# Port_Power.net
KiCad netlist of a schematic drawn in Altium Designer
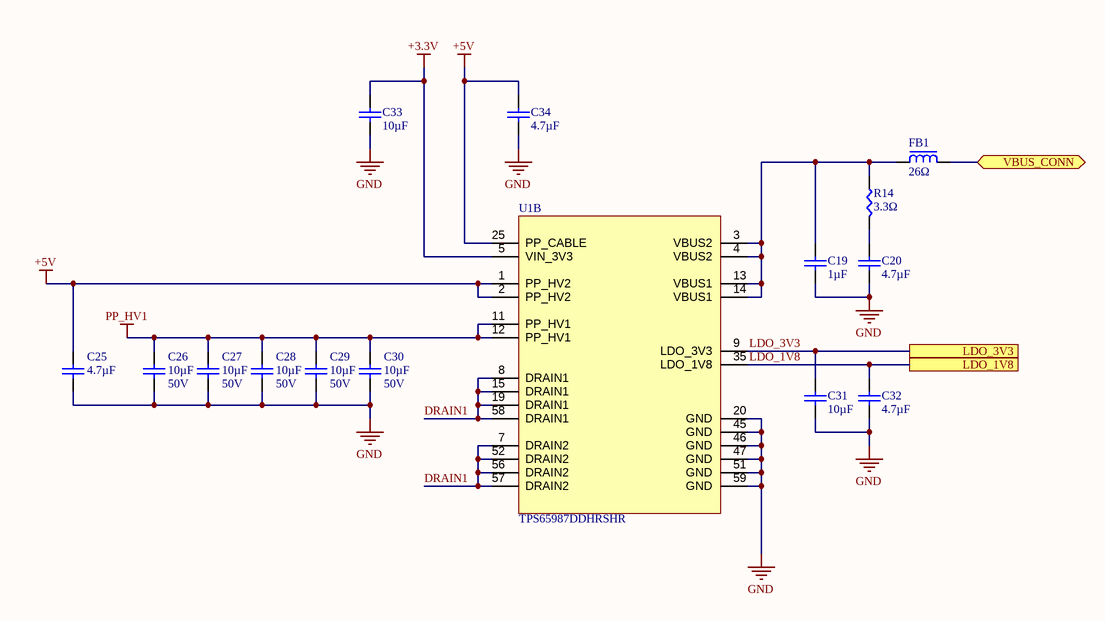
[diagram p0: Port_Power.SchDoc]

(export (version "E")
  (design (tool "Eeschema 10.0.6"))
  (components
    (comp (ref "C19")
      (value "1µF")
      (footprint "CAP0402")
      (description "1 µF ±10% 50V Ceramic Capacitor X5R 0402 (1005 Metric)")
      (fields (field (name "VOLTAGE") "50V") (field (name "Comment") "GRM155R61H105KE05D"))
      (libsource (lib "Schlib1") (part "GRM155R61H105KE05D"))
    )
    (comp (ref "C20")
      (value "4.7µF")
      (footprint "CAP0805")
      (description "4.7 µF ±10% 50V Ceramic Capacitor X5R 0805 (2012 Metric)")
      (fields (field (name "VOLTAGE") "50V") (field (name "Comment") "GRT21BR61H475KE13L"))
      (libsource (lib "Schlib1") (part "GRT21BR61H475KE13L"))
    )
    (comp (ref "C25")
      (value "4.7µF")
      (footprint "CAP0805")
      (description "4.7 µF ±10% 50V Ceramic Capacitor X5R 0805 (2012 Metric)")
      (fields (field (name "VOLTAGE") "50V") (field (name "Comment") "GRT21BR61H475KE13L"))
      (libsource (lib "Schlib1") (part "GRT21BR61H475KE13L"))
    )
    (comp (ref "C26")
      (value "10µF")
      (footprint "CAP1206")
      (description "10 µF ±10% 50V Ceramic Capacitor X5R 1206 (3216 Metric)")
      (fields (field (name "VOLTAGE") "50V") (field (name "Comment") "CL31A106KBHNNNE"))
      (libsource (lib "Schlib1") (part "CL31A106KBHNNNE"))
    )
    (comp (ref "C27")
      (value "10µF")
      (footprint "CAP1206")
      (description "10 µF ±10% 50V Ceramic Capacitor X5R 1206 (3216 Metric)")
      (fields (field (name "VOLTAGE") "50V") (field (name "Comment") "CL31A106KBHNNNE"))
      (libsource (lib "Schlib1") (part "CL31A106KBHNNNE"))
    )
    (comp (ref "C28")
      (value "10µF")
      (footprint "CAP1206")
      (description "10 µF ±10% 50V Ceramic Capacitor X5R 1206 (3216 Metric)")
      (fields (field (name "VOLTAGE") "50V") (field (name "Comment") "CL31A106KBHNNNE"))
      (libsource (lib "Schlib1") (part "CL31A106KBHNNNE"))
    )
    (comp (ref "C29")
      (value "10µF")
      (footprint "CAP1206")
      (description "10 µF ±10% 50V Ceramic Capacitor X5R 1206 (3216 Metric)")
      (fields (field (name "VOLTAGE") "50V") (field (name "Comment") "CL31A106KBHNNNE"))
      (libsource (lib "Schlib1") (part "CL31A106KBHNNNE"))
    )
    (comp (ref "C30")
      (value "10µF")
      (footprint "CAP1206")
      (description "10 µF ±10% 50V Ceramic Capacitor X5R 1206 (3216 Metric)")
      (fields (field (name "VOLTAGE") "50V") (field (name "Comment") "CL31A106KBHNNNE"))
      (libsource (lib "Schlib1") (part "CL31A106KBHNNNE"))
    )
    (comp (ref "C31")
      (value "10µF")
      (footprint "CAP0402")
      (description "10 µF ±20% 6.3V Ceramic Capacitor X5R 0402 (1005 Metric)")
      (fields (field (name "VOLTAGE") "6.3V") (field (name "Comment") "CL05A106MQ5NUNC"))
      (libsource (lib "Schlib1") (part "CL05A106MQ5NUNC"))
    )
    (comp (ref "C32")
      (value "4.7µF")
      (footprint "CAP0805")
      (description "4.7 µF ±10% 50V Ceramic Capacitor X5R 0805 (2012 Metric)")
      (fields (field (name "VOLTAGE") "50V") (field (name "Comment") "GRT21BR61H475KE13L"))
      (libsource (lib "Schlib1") (part "GRT21BR61H475KE13L"))
    )
    (comp (ref "C33")
      (value "10µF")
      (footprint "CAP0402")
      (description "10 µF ±20% 6.3V Ceramic Capacitor X5R 0402 (1005 Metric)")
      (fields (field (name "VOLTAGE") "6.3V") (field (name "Comment") "CL05A106MQ5NUNC"))
      (libsource (lib "Schlib1") (part "CL05A106MQ5NUNC"))
    )
    (comp (ref "C34")
      (value "4.7µF")
      (footprint "CAP0805")
      (description "4.7 µF ±10% 50V Ceramic Capacitor X5R 0805 (2012 Metric)")
      (fields (field (name "VOLTAGE") "50V") (field (name "Comment") "GRT21BR61H475KE13L"))
      (libsource (lib "Schlib1") (part "GRT21BR61H475KE13L"))
    )
    (comp (ref "FB1")
      (value "26Ω")
      (description "26 Ohms @ 100 MHz 1 Power Line Ferrite Bead 0603 (1608 Metric) 6A 7mOhm")
      (fields (field (name "Comment") "BLM18SG260TN1D"))
      (libsource (lib "Schlib1") (part "BLM18SG260TN1D"))
    )
    (comp (ref "R14")
      (value "3.3Ω")
      (footprint "RES0402")
      (fields (field (name "Comment") "ESR10EZPJ3R3"))
      (libsource (lib "Schlib1") (part "ESR10EZPJ3R3"))
    )
    (comp (ref "U1")
      (value "TPS65987DDHRSHR")
      (footprint "56-VQFN (7x7)")
      (description "USB, Type-C Controller PMIC 56-VQFN (7x7)")
      (fields (field (name "MANUFACTURER") "Texas Instruments"))
      (libsource (lib "Schlib1") (part "TPS65987DDHRSHR"))
    )
  )
  (nets
    (net (code "1") (name "+3.3V") (class "Default")
      (node (ref "C33") (pin "2") (pinfunction "2_2") (pintype "passive"))
      (node (ref "U1") (pin "5") (pinfunction "VIN_3V3_5") (pintype "passive"))
    )
    (net (code "2") (name "+5V") (class "Default")
      (node (ref "C25") (pin "1") (pinfunction "1_1") (pintype "passive"))
      (node (ref "C34") (pin "2") (pinfunction "2_2") (pintype "passive"))
      (node (ref "U1") (pin "1") (pinfunction "PP_HV2_1") (pintype "passive"))
      (node (ref "U1") (pin "2") (pinfunction "PP_HV2_2") (pintype "passive"))
      (node (ref "U1") (pin "25") (pinfunction "PP_CABLE_25") (pintype "passive"))
    )
    (net (code "3") (name "/DRAIN1") (class "Default")
      (node (ref "U1") (pin "15") (pinfunction "DRAIN1_15") (pintype "passive"))
      (node (ref "U1") (pin "19") (pinfunction "DRAIN1_19") (pintype "passive"))
      (node (ref "U1") (pin "52") (pinfunction "DRAIN2_52") (pintype "passive"))
      (node (ref "U1") (pin "56") (pinfunction "DRAIN2_56") (pintype "passive"))
      (node (ref "U1") (pin "57") (pinfunction "DRAIN2_57") (pintype "passive"))
      (node (ref "U1") (pin "58") (pinfunction "DRAIN1_58") (pintype "passive"))
      (node (ref "U1") (pin "7") (pinfunction "DRAIN2_7") (pintype "passive"))
      (node (ref "U1") (pin "8") (pinfunction "DRAIN1_8") (pintype "passive"))
    )
    (net (code "4") (name "/LDO_1V8") (class "Default")
      (node (ref "C32") (pin "2") (pinfunction "2_2") (pintype "passive"))
      (node (ref "U1") (pin "35") (pinfunction "LDO_1V8_35") (pintype "passive"))
    )
    (net (code "5") (name "/LDO_3V3") (class "Default")
      (node (ref "C31") (pin "2") (pinfunction "2_2") (pintype "passive"))
      (node (ref "U1") (pin "9") (pinfunction "LDO_3V3_9") (pintype "passive"))
    )
    (net (code "6") (name "/VBUS_CONN") (class "Default")
      (node (ref "FB1") (pin "2") (pinfunction "2_2") (pintype "passive"))
    )
    (net (code "7") (name "GND") (class "Default")
      (node (ref "C19") (pin "1") (pinfunction "1_1") (pintype "passive"))
      (node (ref "C20") (pin "1") (pinfunction "1_1") (pintype "passive"))
      (node (ref "C25") (pin "2") (pinfunction "2_2") (pintype "passive"))
      (node (ref "C26") (pin "1") (pinfunction "1_1") (pintype "passive"))
      (node (ref "C27") (pin "1") (pinfunction "1_1") (pintype "passive"))
      (node (ref "C28") (pin "1") (pinfunction "1_1") (pintype "passive"))
      (node (ref "C29") (pin "1") (pinfunction "1_1") (pintype "passive"))
      (node (ref "C30") (pin "1") (pinfunction "1_1") (pintype "passive"))
      (node (ref "C31") (pin "1") (pinfunction "1_1") (pintype "passive"))
      (node (ref "C32") (pin "1") (pinfunction "1_1") (pintype "passive"))
      (node (ref "C33") (pin "1") (pinfunction "1_1") (pintype "passive"))
      (node (ref "C34") (pin "1") (pinfunction "1_1") (pintype "passive"))
      (node (ref "U1") (pin "20") (pinfunction "GND_20") (pintype "passive"))
      (node (ref "U1") (pin "45") (pinfunction "GND_45") (pintype "passive"))
      (node (ref "U1") (pin "46") (pinfunction "GND_46") (pintype "passive"))
      (node (ref "U1") (pin "47") (pinfunction "GND_47") (pintype "passive"))
      (node (ref "U1") (pin "51") (pinfunction "GND_51") (pintype "passive"))
      (node (ref "U1") (pin "59") (pinfunction "GND_59") (pintype "passive"))
    )
    (net (code "8") (name "Net-(C19-Pad2)") (class "Default")
      (node (ref "C19") (pin "2") (pinfunction "2_2") (pintype "passive"))
      (node (ref "FB1") (pin "1") (pinfunction "1_1") (pintype "passive"))
      (node (ref "R14") (pin "2") (pinfunction "2_2") (pintype "passive"))
      (node (ref "U1") (pin "13") (pinfunction "VBUS1_13") (pintype "passive"))
      (node (ref "U1") (pin "14") (pinfunction "VBUS1_14") (pintype "passive"))
      (node (ref "U1") (pin "3") (pinfunction "VBUS2_3") (pintype "passive"))
      (node (ref "U1") (pin "4") (pinfunction "VBUS2_4") (pintype "passive"))
    )
    (net (code "9") (name "Net-(C20-Pad2)") (class "Default")
      (node (ref "C20") (pin "2") (pinfunction "2_2") (pintype "passive"))
      (node (ref "R14") (pin "1") (pinfunction "1_1") (pintype "passive"))
    )
    (net (code "10") (name "PP_HV1") (class "Default")
      (node (ref "C26") (pin "2") (pinfunction "2_2") (pintype "passive"))
      (node (ref "C27") (pin "2") (pinfunction "2_2") (pintype "passive"))
      (node (ref "C28") (pin "2") (pinfunction "2_2") (pintype "passive"))
      (node (ref "C29") (pin "2") (pinfunction "2_2") (pintype "passive"))
      (node (ref "C30") (pin "2") (pinfunction "2_2") (pintype "passive"))
      (node (ref "U1") (pin "11") (pinfunction "PP_HV1_11") (pintype "passive"))
      (node (ref "U1") (pin "12") (pinfunction "PP_HV1_12") (pintype "passive"))
    )
  )
)
